# Flyback-Converter_sch.net
KiCad netlist of a schematic drawn in Altium Designer
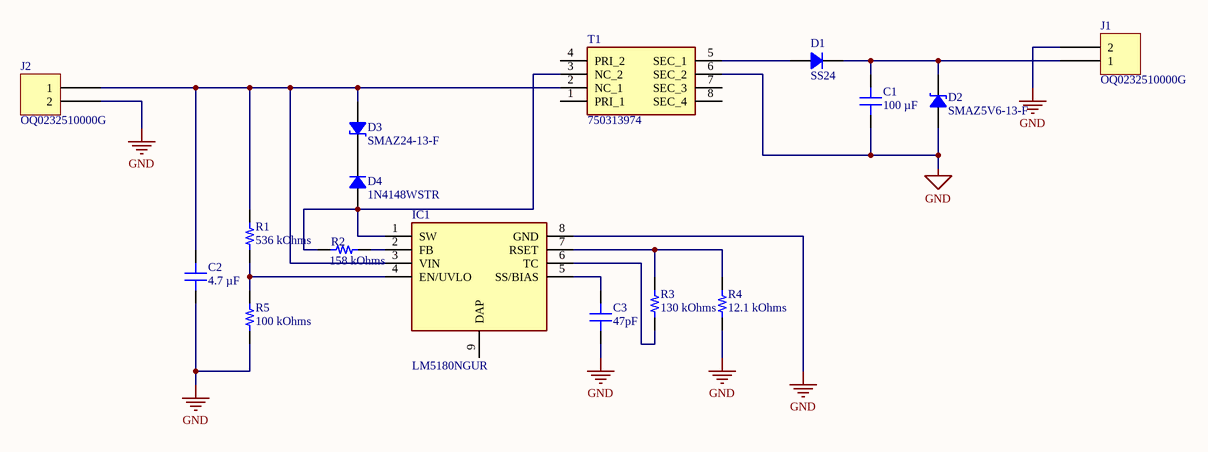
[diagram p0: Flyback-Converter_sch.SchDoc]

(export (version "E")
  (design (tool "Eeschema 10.0.6"))
  (components
    (comp (ref "C1")
      (value "100 µF")
      (footprint "CAP 1210_3225 - 1MM")
      (description "CAP CER 100UF 6.3V X7S 1210")
      (fields
        (field (name "PART NUMBER") "GRM32EC70J107ME15L")
        (field (name "MANUFACTURER") "Murata Electronics")
      )
      (libsource (lib "Celestial Altium Library - altium_library") (part "Capacitor"))
    )
    (comp (ref "C2")
      (value "4.7 µF")
      (footprint "CAP 1210_3225 - 1MM")
      (description "CAP CER 4.7UF 100V X5R 1210")
      (fields (field (name "PART NUMBER") "HMK325BJ475KM-PE") (field (name "MANUFACTURER") "Taiyo Yuden"))
      (libsource (lib "Celestial Altium Library - altium_library") (part "Capacitor"))
    )
    (comp (ref "C3")
      (value "47pF")
      (footprint "CAP 0402_1005")
      (description "CAP CER 47PF 50V NP0 0402")
      (fields (field (name "PART NUMBER") "04025A470GAT2A") (field (name "MANUFACTURER") "AVX Corporation"))
      (libsource (lib "Celestial Altium Library - altium_library") (part "Capacitor"))
    )
    (comp (ref "D1")
      (value "SS24")
      (footprint "DO214AA SMB")
      (description "DIODE SCHOTTKY 40V 2A DO214AA")
      (fields (field (name "MANUFACTURER") "ON Semiconductor"))
      (libsource (lib "Celestial Altium Library - altium_library") (part "Diode"))
    )
    (comp (ref "D2")
      (value "SMAZ5V6-13-F")
      (footprint "DO214AC SMA")
      (description "DIODE ZENER 5.6V 1W SMA")
      (fields (field (name "MANUFACTURER") "Diodes Incorporated") (field (name "TOLERANCE") "±5%"))
      (libsource (lib "Celestial Altium Library - altium_library") (part "Diode Zener"))
    )
    (comp (ref "D3")
      (value "SMAZ24-13-F")
      (footprint "DO214AC SMA")
      (description "DIODE ZENER 24V 1W SMA")
      (fields (field (name "MANUFACTURER") "Diodes Incorporated") (field (name "TOLERANCE") "±5%"))
      (libsource (lib "Celestial Altium Library - altium_library") (part "Diode Zener"))
    )
    (comp (ref "D4")
      (value "1N4148WSTR")
      (footprint "SOD323F")
      (description "DIODE GEN PURP 75V 300MA SOD323")
      (fields (field (name "MANUFACTURER") "SMC Diode Solutions"))
      (libsource (lib "Celestial Altium Library - altium_library") (part "Diode"))
    )
    (comp (ref "IC1")
      (value "LM5180NGUR")
      (footprint "SamacSys:SON80P400X400X80-9N")
      (description "Integrated Circuit")
      (fields (field (name "MOUSER PART NUMBER") "595-LM5180NGUR"))
      (libsource (lib "*") (part "LM5180NGUR"))
    )
    (comp (ref "J1")
      (value "OQ0232510000G")
      (footprint "FCI 06-381-2PIN")
      (description "TERM BLOCK HDR 2POS 90DEG 3.81MM")
      (fields (field (name "MANUFACTURER") "Amphenol Anytek"))
      (libsource (lib "") (part "2 Pin_1"))
    )
    (comp (ref "J2")
      (value "OQ0232510000G")
      (footprint "FCI 06-381-2PIN")
      (description "TERM BLOCK HDR 2POS 90DEG 3.81MM")
      (fields (field (name "MANUFACTURER") "Amphenol Anytek"))
      (libsource (lib "Celestial Altium Library - altium_library") (part "2 Pin"))
    )
    (comp (ref "R1")
      (value "536 kOhms")
      (footprint "RES 0603_1608")
      (description "RES 536 KOHM 0.1% 1/16W 0603")
      (fields
        (field (name "PART NUMBER") "CPF0603B536KE1")
        (field (name "MANUFACTURER") "TE Connectivity Passive Product")
      )
      (libsource (lib "Celestial Altium Library - altium_library") (part "Resistor"))
    )
    (comp (ref "R2")
      (value "158 kOhms")
      (footprint "RES 0402_1005")
      (description "RES SMD 158K OHM 1% 1/16W 0402")
      (fields (field (name "PART NUMBER") "AC0402FR-07158KL") (field (name "MANUFACTURER") "Yageo"))
      (libsource (lib "Celestial Altium Library - altium_library") (part "Resistor"))
    )
    (comp (ref "R3")
      (value "130 kOhms")
      (footprint "RES 0402_1005")
      (description "RES SMD 130K OHM 1% 1/16W 0402")
      (fields (field (name "PART NUMBER") "RT0402FRE07130KL") (field (name "MANUFACTURER") "Yageo"))
      (libsource (lib "Celestial Altium Library - altium_library") (part "Resistor"))
    )
    (comp (ref "R4")
      (value "12.1 kOhms")
      (footprint "RES 0402_1005")
      (description "RES 12.1K OHM 1% 1/16W 0402")
      (fields (field (name "PART NUMBER") "RC0402FR-1012K1L") (field (name "MANUFACTURER") "Yageo"))
      (libsource (lib "Celestial Altium Library - altium_library") (part "Resistor"))
    )
    (comp (ref "R5")
      (value "100 kOhms")
      (footprint "RES 0402_1005")
      (description "RES SMD 100K OHM 5% 1/16W 0402")
      (fields (field (name "PART NUMBER") "CRCW0402100KJNEDIF") (field (name "MANUFACTURER") "Vishay Dale"))
      (libsource (lib "Celestial Altium Library - altium_library") (part "Resistor"))
    )
    (comp (ref "T1")
      (value "750313974")
      (footprint "SamacSys:750313445")
      (description "Transformer")
      (fields (field (name "MOUSER PART NUMBER") "710-750313974"))
      (libsource (lib "*") (part "750313974"))
    )
  )
  (nets
    (net (code "1") (name "GND") (class "Default")
      (node (ref "C1") (pin "1") (pinfunction "1_1") (pintype "passive"))
      (node (ref "C2") (pin "1") (pinfunction "1_1") (pintype "passive"))
      (node (ref "C3") (pin "1") (pinfunction "1_1") (pintype "passive"))
      (node (ref "D2") (pin "1") (pinfunction "1_1") (pintype "passive"))
      (node (ref "IC1") (pin "8") (pinfunction "GND_8") (pintype "passive"))
      (node (ref "J1") (pin "2") (pinfunction "2_2") (pintype "passive"))
      (node (ref "J2") (pin "2") (pinfunction "2_2") (pintype "passive"))
      (node (ref "R4") (pin "1") (pinfunction "1_1") (pintype "passive"))
      (node (ref "R5") (pin "1") (pinfunction "1_1") (pintype "passive"))
      (node (ref "T1") (pin "6") (pinfunction "SEC_2_6") (pintype "passive"))
    )
    (net (code "2") (name "Net-(C1-Pad2)") (class "Default")
      (node (ref "C1") (pin "2") (pinfunction "2_2") (pintype "passive"))
      (node (ref "D1") (pin "2") (pinfunction "2_2") (pintype "passive"))
      (node (ref "D2") (pin "2") (pinfunction "2_2") (pintype "passive"))
      (node (ref "J1") (pin "1") (pinfunction "1_1") (pintype "passive"))
    )
    (net (code "3") (name "Net-(D3-Pad2)") (class "Default")
      (node (ref "D3") (pin "2") (pinfunction "2_2") (pintype "passive"))
      (node (ref "D4") (pin "2") (pinfunction "2_2") (pintype "passive"))
    )
    (net (code "4") (name "Net-(IC1-EN{slash}UVLO)") (class "Default")
      (node (ref "IC1") (pin "4") (pinfunction "EN/UVLO_4") (pintype "passive"))
      (node (ref "R1") (pin "1") (pinfunction "1_1") (pintype "passive"))
      (node (ref "R5") (pin "2") (pinfunction "2_2") (pintype "passive"))
    )
    (net (code "5") (name "Net-(IC1-FB)") (class "Default")
      (node (ref "IC1") (pin "2") (pinfunction "FB_2") (pintype "passive"))
      (node (ref "R2") (pin "1") (pinfunction "1_1") (pintype "passive"))
    )
    (net (code "6") (name "Net-(IC1-RSET)") (class "Default")
      (node (ref "IC1") (pin "7") (pinfunction "RSET_7") (pintype "passive"))
      (node (ref "R3") (pin "2") (pinfunction "2_2") (pintype "passive"))
      (node (ref "R4") (pin "2") (pinfunction "2_2") (pintype "passive"))
    )
    (net (code "7") (name "Net-(IC1-SS{slash}BIAS)") (class "Default")
      (node (ref "C3") (pin "2") (pinfunction "2_2") (pintype "passive"))
      (node (ref "IC1") (pin "5") (pinfunction "SS/BIAS_5") (pintype "passive"))
    )
    (net (code "8") (name "Net-(IC1-SW)") (class "Default")
      (node (ref "D4") (pin "1") (pinfunction "1_1") (pintype "passive"))
      (node (ref "IC1") (pin "1") (pinfunction "SW_1") (pintype "passive"))
      (node (ref "R2") (pin "2") (pinfunction "2_2") (pintype "passive"))
      (node (ref "T1") (pin "3") (pinfunction "NC_2_3") (pintype "passive"))
    )
    (net (code "9") (name "Net-(IC1-TC)") (class "Default")
      (node (ref "IC1") (pin "6") (pinfunction "TC_6") (pintype "passive"))
      (node (ref "R3") (pin "1") (pinfunction "1_1") (pintype "passive"))
    )
    (net (code "10") (name "Net-(IC1-VIN)") (class "Default")
      (node (ref "C2") (pin "2") (pinfunction "2_2") (pintype "passive"))
      (node (ref "D3") (pin "1") (pinfunction "1_1") (pintype "passive"))
      (node (ref "IC1") (pin "3") (pinfunction "VIN_3") (pintype "passive"))
      (node (ref "J2") (pin "1") (pinfunction "1_1") (pintype "passive"))
      (node (ref "R1") (pin "2") (pinfunction "2_2") (pintype "passive"))
      (node (ref "T1") (pin "2") (pinfunction "NC_1_2") (pintype "passive"))
    )
    (net (code "11") (name "Net-(T1-SEC_1)") (class "Default")
      (node (ref "D1") (pin "1") (pinfunction "1_1") (pintype "passive"))
      (node (ref "T1") (pin "5") (pinfunction "SEC_1_5") (pintype "passive"))
    )
    (net (code "12") (name "unconnected-(IC1-DAP-Pad9)") (class "Default")
      (node (ref "IC1") (pin "9") (pinfunction "DAP_9") (pintype "passive"))
    )
    (net (code "13") (name "unconnected-(T1-PRI_1-Pad1)") (class "Default")
      (node (ref "T1") (pin "1") (pinfunction "PRI_1_1") (pintype "passive"))
    )
    (net (code "14") (name "unconnected-(T1-PRI_2-Pad4)") (class "Default")
      (node (ref "T1") (pin "4") (pinfunction "PRI_2_4") (pintype "passive"))
    )
    (net (code "15") (name "unconnected-(T1-SEC_3-Pad7)") (class "Default")
      (node (ref "T1") (pin "7") (pinfunction "SEC_3_7") (pintype "passive"))
    )
    (net (code "16") (name "unconnected-(T1-SEC_4-Pad8)") (class "Default")
      (node (ref "T1") (pin "8") (pinfunction "SEC_4_8") (pintype "passive"))
    )
  )
)
